# SHT_2_Power_07349-R5_L10.net
KiCad netlist of a schematic drawn in Altium Designer
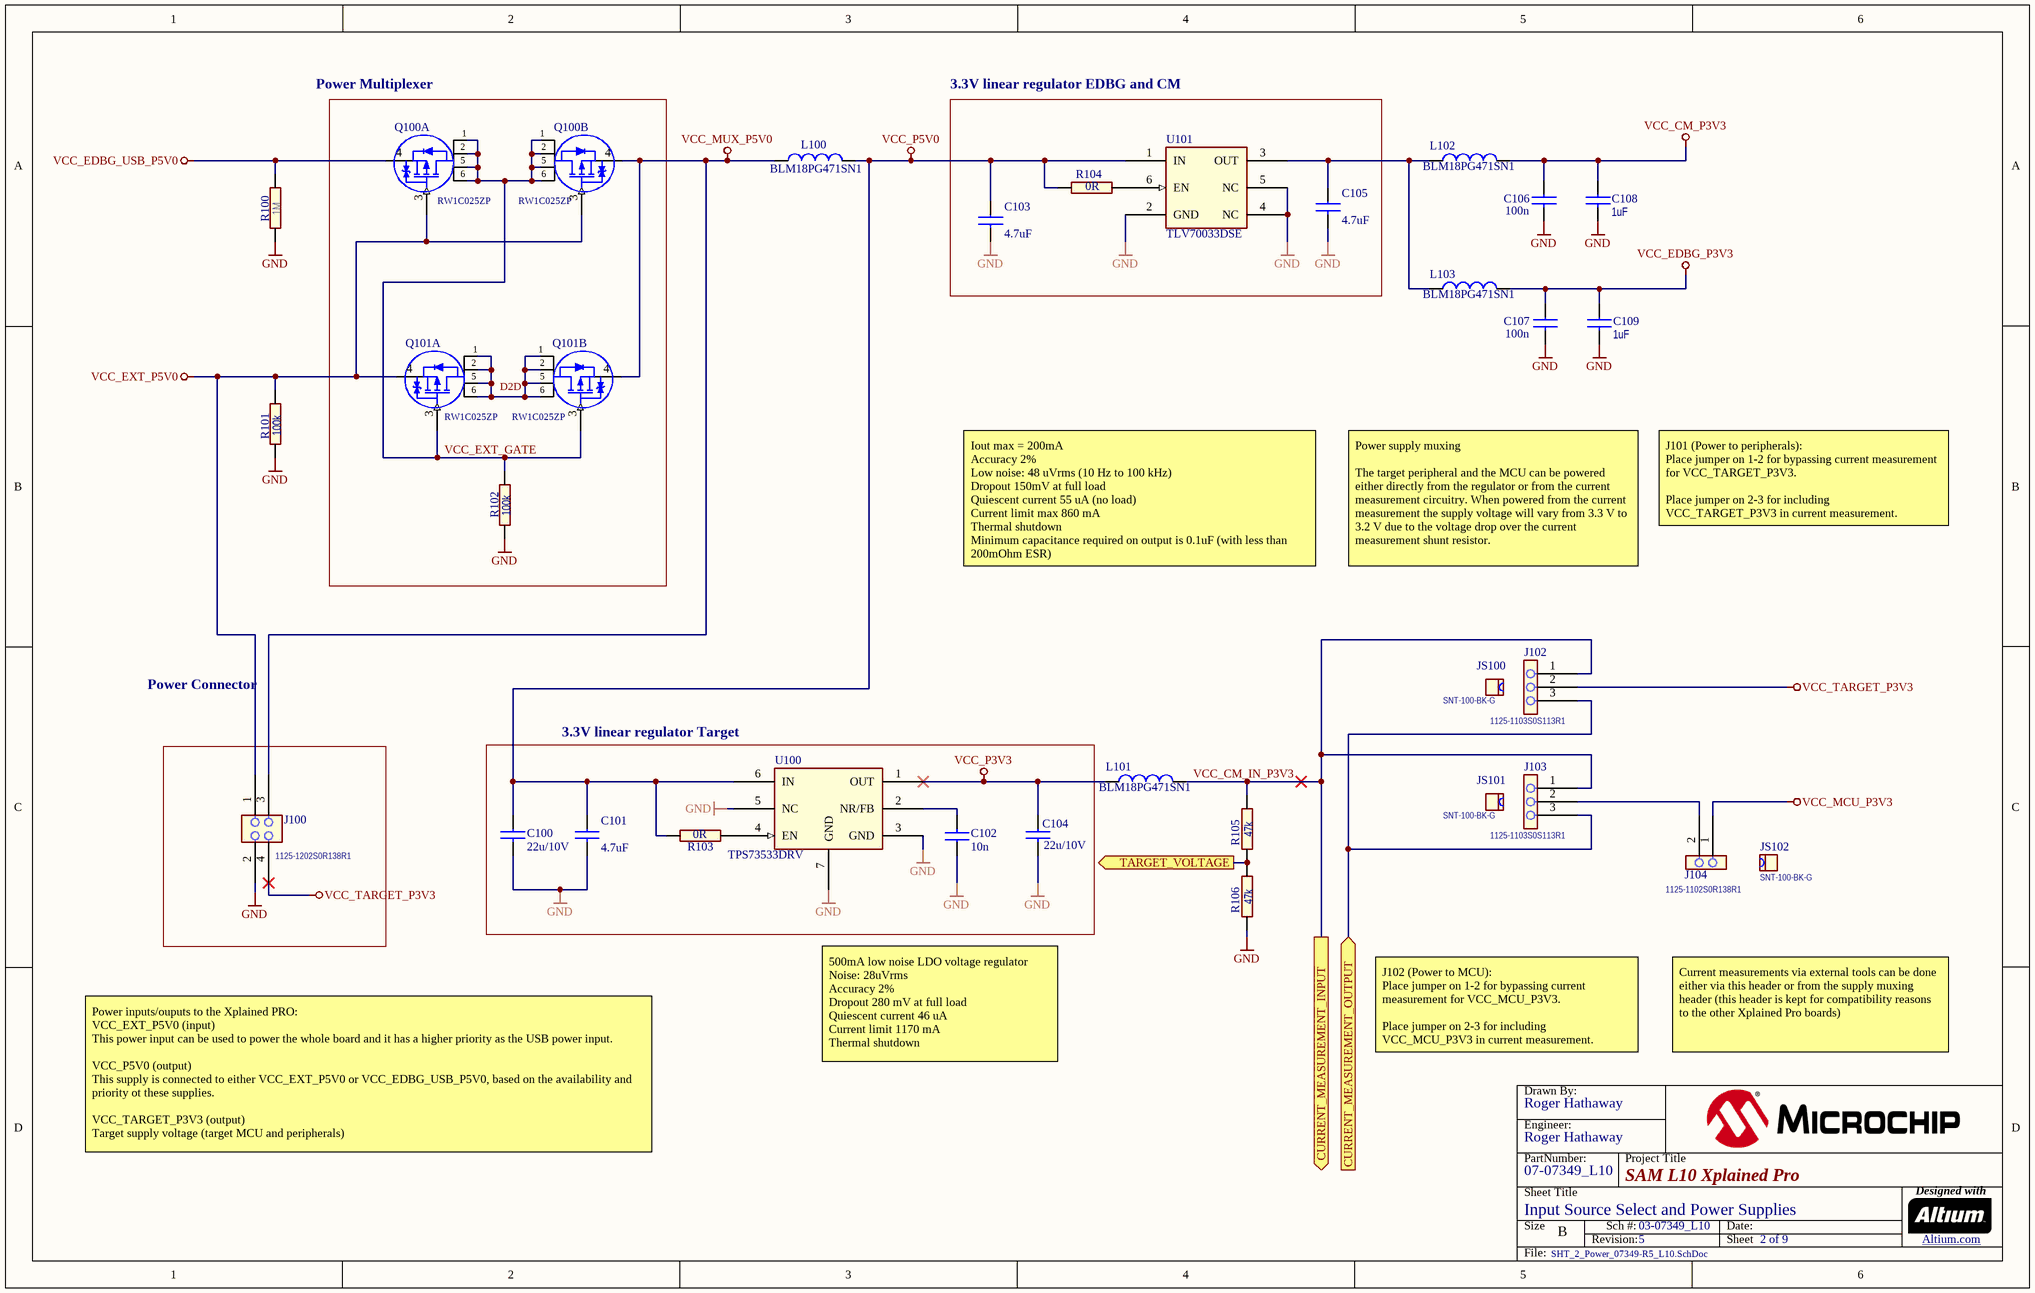
[diagram p0: SHT_2_Power_07349-R5_L10.SchDoc]

(export (version "E")
  (design (tool "Eeschema 10.0.6"))
  (components
    (comp (ref "C100")
      (value "22u/10V")
      (footprint "AP1-00003")
      (description "Ceramic capacitor, SMD 0805, X5R, 10V, Â±20%")
      (fields
        (field (name "MANUFACTURER") "tdk")
        (field (name "MPN") "C2012X5R1A226M/0.85")
        (field (name "VERIFIED BY") "Lars Helge Mo")
      )
      (libsource (lib "AltiumDbLib") (part "CAP-NONPOL"))
    )
    (comp (ref "C101")
      (value "4.7uF")
      (footprint "AltiumDbLib:AP1-00117")
      (description "Ceramic capacitor, SMD 0603, X5R, 10V, 10% (de31036)")
      (fields
        (field (name "TOLERANCE") "10%")
        (field (name "MANUFACTURER") "tdk")
        (field (name "VERIFIED BY") "Lars Helge Mo")
      )
      (libsource (lib "AltiumDbLib") (part "CAP-NONPOL"))
    )
    (comp (ref "C102")
      (value "10n")
      (footprint "AltiumDbLib:AP1-00053")
      (description "Ceramic capacitor, SMD 0402, X7R, 25V, +/-10%")
      (fields
        (field (name "TOLERANCE") "25V, +/-10%")
        (field (name "MANUFACTURER") "YAGEO CORP")
        (field (name "VERIFIED BY") "Lars Helge Mo")
      )
      (libsource (lib "AltiumDbLib") (part "CAP-NONPOL"))
    )
    (comp (ref "C103")
      (value "4.7uF")
      (footprint "AltiumDbLib:AP1-00117")
      (description "Ceramic capacitor, SMD 0603, X5R, 10V, 10% (de31036)")
      (fields
        (field (name "TOLERANCE") "10%")
        (field (name "MANUFACTURER") "tdk")
        (field (name "VERIFIED BY") "Lars Helge Mo")
      )
      (libsource (lib "AltiumDbLib") (part "CAP-NONPOL"))
    )
    (comp (ref "C104")
      (value "22u/10V")
      (footprint "AP1-00003")
      (description "Ceramic capacitor, SMD 0805, X5R, 10V, Â±20%")
      (fields
        (field (name "MANUFACTURER") "tdk")
        (field (name "MPN") "C2012X5R1A226M/0.85")
        (field (name "VERIFIED BY") "Lars Helge Mo")
      )
      (libsource (lib "AltiumDbLib") (part "CAP-NONPOL"))
    )
    (comp (ref "C105")
      (value "4.7uF")
      (footprint "AltiumDbLib:AP1-00117")
      (description "Ceramic capacitor, SMD 0603, X5R, 10V, 10% (de31036)")
      (fields
        (field (name "TOLERANCE") "10%")
        (field (name "MANUFACTURER") "tdk")
        (field (name "VERIFIED BY") "Lars Helge Mo")
      )
      (libsource (lib "AltiumDbLib") (part "CAP-NONPOL"))
    )
    (comp (ref "C106")
      (value "100n")
      (footprint "AltiumDbLib:AP1-00053")
      (description "Ceramic capacitor, SMD 0402, X7R, 16V, +/-10%")
      (fields
        (field (name "TOLERANCE") "16V, +/-10%")
        (field (name "MANUFACTURER") "Kemet")
        (field (name "VERIFIED BY") "Lars Helge Mo")
      )
      (libsource (lib "AltiumDbLib") (part "CAP-NONPOL"))
    )
    (comp (ref "C107")
      (value "100n")
      (footprint "AltiumDbLib:AP1-00053")
      (description "Ceramic capacitor, SMD 0402, X7R, 16V, +/-10%")
      (fields
        (field (name "TOLERANCE") "16V, +/-10%")
        (field (name "MANUFACTURER") "Kemet")
        (field (name "VERIFIED BY") "Lars Helge Mo")
      )
      (libsource (lib "AltiumDbLib") (part "CAP-NONPOL"))
    )
    (comp (ref "C108")
      (value "1uF")
      (footprint "AP1-00002")
      (description "Ceramic capacitor, SMD 0603, X5R, 25V, ±10%")
      (fields
        (field (name "TOLERANCE") "±10%")
        (field (name "MANUFACTURER") "Murata")
        (field (name "VERIFIED BY") "Lars Helge Mo")
      )
      (libsource (lib "AltiumDbLib") (part "CAP-NONPOL"))
    )
    (comp (ref "C109")
      (value "1uF")
      (footprint "AP1-00002")
      (description "Ceramic capacitor, SMD 0603, X5R, 25V, ±10%")
      (fields
        (field (name "TOLERANCE") "±10%")
        (field (name "MANUFACTURER") "Murata")
        (field (name "VERIFIED BY") "Lars Helge Mo")
      )
      (libsource (lib "AltiumDbLib") (part "CAP-NONPOL"))
    )
    (comp (ref "J100")
      (value "1125-1202S0R138R1")
      (footprint "AP8-01076")
      (description "Pin header, 2x2, Right Angle, 2.54mm, THT, Pin In Paste")
      (fields
        (field (name "MANUFACTURER") "WCON HARDWARE ELECTRONICS CO., LTD")
        (field (name "Comment") "HEADER 2x2")
        (field (name "VERIFIED BY") "Lars Helge Mo")
      )
      (libsource (lib "AltiumDbLib") (part "HEADER 2x2"))
    )
    (comp (ref "J102")
      (value "1125-1103S0S113R1")
      (footprint "AP8-01075")
      (description "1x3 pin header, 2.54mm pitch, Pin-in-Paste THM")
      (fields
        (field (name "MANUFACTURER") "WCON HARDWARE ELECTRONICS CO., LTD")
        (field (name "Comment") "HEADER 1x3")
        (field (name "VERIFIED BY") "Lars Helge Mo")
      )
      (libsource (lib "AltiumDbLib") (part "HEADER 1x3"))
    )
    (comp (ref "J103")
      (value "1125-1103S0S113R1")
      (footprint "AP8-01075")
      (description "1x3 pin header, 2.54mm pitch, Pin-in-Paste THM")
      (fields
        (field (name "MANUFACTURER") "WCON HARDWARE ELECTRONICS CO., LTD")
        (field (name "Comment") "HEADER 1x3")
        (field (name "VERIFIED BY") "Lars Helge Mo")
      )
      (libsource (lib "AltiumDbLib") (part "HEADER 1x3"))
    )
    (comp (ref "J104")
      (value "Low cost replacement for A08-0764")
      (footprint "AP8-01071")
      (description "1x2 pin header, right angle, 2.54 mm pitch, through-hole")
      (fields
        (field (name "MANUFACTURER") "WCON HARDWARE ELECTRONICS CO., LTD")
        (field (name "MPN") "1125-1102S0R138R1")
        (field (name "VERIFIED BY") "Lars Helge")
      )
      (libsource (lib "AltiumDbLib") (part "HEADER 1x2"))
    )
    (comp (ref "JS100")
      (value "SNT-100-BK-G")
      (footprint "AP8-00525")
      (description "Jumper cap for 2.54mm pinheader")
      (fields
        (field (name "MANUFACTURER") "SAMTEC")
        (field (name "Comment") "To be used by request from ESCATEC")
        (field (name "VERIFIED BY") "Lars Helge Mo")
      )
      (libsource (lib "AltiumDbLib") (part "JUMPER_CAP"))
    )
    (comp (ref "JS101")
      (value "SNT-100-BK-G")
      (footprint "AP8-00525")
      (description "Jumper cap for 2.54mm pinheader")
      (fields
        (field (name "MANUFACTURER") "SAMTEC")
        (field (name "Comment") "To be used by request from ESCATEC")
        (field (name "VERIFIED BY") "Lars Helge Mo")
      )
      (libsource (lib "AltiumDbLib") (part "JUMPER_CAP"))
    )
    (comp (ref "JS102")
      (value "SNT-100-BK-G")
      (footprint "AP8-00525")
      (description "Jumper cap for 2.54mm pinheader")
      (fields
        (field (name "MANUFACTURER") "SAMTEC")
        (field (name "Comment") "To be used by request from ESCATEC")
        (field (name "VERIFIED BY") "Lars Helge Mo")
      )
      (libsource (lib "") (part "JUMPER_CAP_1"))
    )
    (comp (ref "L100")
      (value "BLM18PG471SN1")
      (footprint "AP3-00005")
      (description "SMD RF inductor 0603. Z=470Ohm (@100MHz), Max R(dc)=0.65Ohm, Max current=1A")
      (fields
        (field (name "TOLERANCE") "±25%")
        (field (name "MANUFACTURER") "Murata")
        (field (name "VERIFIED BY") "Lars Helge Mo")
      )
      (libsource (lib "") (part "INDUCTOR_1"))
    )
    (comp (ref "L101")
      (value "BLM18PG471SN1")
      (footprint "AP3-00005")
      (description "SMD RF inductor 0603. Z=470Ohm (@100MHz), Max R(dc)=0.65Ohm, Max current=1A")
      (fields
        (field (name "TOLERANCE") "±25%")
        (field (name "MANUFACTURER") "Murata")
        (field (name "VERIFIED BY") "Lars Helge Mo")
      )
      (libsource (lib "AltiumDbLib") (part "INDUCTOR"))
    )
    (comp (ref "L102")
      (value "BLM18PG471SN1")
      (footprint "AP3-00005")
      (description "SMD RF inductor 0603. Z=470Ohm (@100MHz), Max R(dc)=0.65Ohm, Max current=1A")
      (fields
        (field (name "TOLERANCE") "±25%")
        (field (name "MANUFACTURER") "Murata")
        (field (name "VERIFIED BY") "Lars Helge Mo")
      )
      (libsource (lib "") (part "INDUCTOR_1"))
    )
    (comp (ref "L103")
      (value "BLM18PG471SN1")
      (footprint "AP3-00005")
      (description "SMD RF inductor 0603. Z=470Ohm (@100MHz), Max R(dc)=0.65Ohm, Max current=1A")
      (fields
        (field (name "TOLERANCE") "±25%")
        (field (name "MANUFACTURER") "Murata")
        (field (name "VERIFIED BY") "Lars Helge Mo")
      )
      (libsource (lib "") (part "INDUCTOR_1"))
    )
    (comp (ref "Q100A")
      (value "MOSFET_RW1C025ZP")
      (footprint "AP5-00057")
      (description "Pch -20V -2.5A Small Signal MOSFET")
      (fields
        (field (name "MANUFACTURER") "ROHM")
        (field (name "MPN") "RW1C025ZP")
        (field (name "MANUFACTURER PART NUMBER") "RW1C025ZP")
      )
      (libsource (lib "") (part "MOSFET_RW1C025ZP_1"))
    )
    (comp (ref "Q100B")
      (value "MOSFET_RW1C025ZP")
      (footprint "AP5-00057")
      (description "Pch -20V -2.5A Small Signal MOSFET")
      (fields
        (field (name "MANUFACTURER") "ROHM")
        (field (name "MPN") "RW1C025ZP")
        (field (name "MANUFACTURER PART NUMBER") "RW1C025ZP")
      )
      (libsource (lib "AltiumDbLib") (part "MOSFET_RW1C025ZP"))
    )
    (comp (ref "Q101A")
      (value "MOSFET_RW1C025ZP")
      (footprint "AP5-00057")
      (description "Pch -20V -2.5A Small Signal MOSFET")
      (fields
        (field (name "MANUFACTURER") "ROHM")
        (field (name "MPN") "RW1C025ZP")
        (field (name "MANUFACTURER PART NUMBER") "RW1C025ZP")
      )
      (libsource (lib "") (part "MOSFET_RW1C025ZP_1"))
    )
    (comp (ref "Q101B")
      (value "MOSFET_RW1C025ZP")
      (footprint "AP5-00057")
      (description "Pch -20V -2.5A Small Signal MOSFET")
      (fields
        (field (name "MANUFACTURER") "ROHM")
        (field (name "MPN") "RW1C025ZP")
        (field (name "MANUFACTURER PART NUMBER") "RW1C025ZP")
      )
      (libsource (lib "AltiumDbLib") (part "MOSFET_RW1C025ZP"))
    )
    (comp (ref "R100")
      (value "1M")
      (footprint "AltiumDbLib:AP2-00011")
      (description "Thick film resistror, SMD 0402, 1/16W, 1%")
      (fields
        (field (name "TOLERANCE") "1%")
        (field (name "MANUFACTURER") "YAGEO CORP")
        (field (name "VERIFIED BY") "Lars Helge Mo")
      )
      (libsource (lib "") (part "R2_2"))
    )
    (comp (ref "R101")
      (value "100k")
      (footprint "AltiumDbLib:AP2-00011")
      (description "Thick film resistor, SMD 0402, 1/16W, 1%")
      (fields
        (field (name "TOLERANCE") "1 %")
        (field (name "MANUFACTURER") "ASJ")
        (field (name "VERIFIED BY") "Lars Helge Mo")
      )
      (libsource (lib "") (part "R2_1"))
    )
    (comp (ref "R102")
      (value "100k")
      (footprint "AltiumDbLib:AP2-00011")
      (description "Thick film resistor, SMD 0402, 1/16W, 1%")
      (fields
        (field (name "TOLERANCE") "1 %")
        (field (name "MANUFACTURER") "ASJ")
        (field (name "VERIFIED BY") "Lars Helge Mo")
      )
      (libsource (lib "") (part "R2_1"))
    )
    (comp (ref "R103")
      (value "0R")
      (footprint "AltiumDbLib:AP2-00011")
      (description "RES 0.0 OHM 1/16W 0402 SMD")
      (fields
        (field (name "TOLERANCE") "1 %")
        (field (name "MANUFACTURER") "(n/a)")
        (field (name "VERIFIED BY") "Lars Helge Mo")
      )
      (libsource (lib "AltiumDbLib") (part "R2"))
    )
    (comp (ref "R104")
      (value "0R")
      (footprint "AltiumDbLib:AP2-00011")
      (description "RES 0.0 OHM 1/16W 0402 SMD")
      (fields
        (field (name "TOLERANCE") "1 %")
        (field (name "MANUFACTURER") "(n/a)")
        (field (name "VERIFIED BY") "Lars Helge Mo")
      )
      (libsource (lib "AltiumDbLib") (part "R2"))
    )
    (comp (ref "R105")
      (value "47k")
      (footprint "AltiumDbLib:AP2-00011")
      (description "Thick film resistor, SMD 0402, 1/16W, 1%")
      (fields
        (field (name "TOLERANCE") "1 %")
        (field (name "MANUFACTURER") "KOA")
        (field (name "VERIFIED BY") "Lars Helge Mo")
      )
      (libsource (lib "") (part "R2_1"))
    )
    (comp (ref "R106")
      (value "47k")
      (footprint "AltiumDbLib:AP2-00011")
      (description "Thick film resistor, SMD 0402, 1/16W, 1%")
      (fields
        (field (name "TOLERANCE") "1 %")
        (field (name "MANUFACTURER") "KOA")
        (field (name "VERIFIED BY") "Lars Helge Mo")
      )
      (libsource (lib "") (part "R2_1"))
    )
    (comp (ref "U100")
      (value "TPS73533DRV")
      (footprint "AP6-00162")
      (fields (field (name "MANUFACTURER") "Texas Instruments"))
      (libsource (lib "AltiumDbLib") (part "TPS735xxDRV"))
    )
    (comp (ref "U101")
      (value "TLV70033DSE")
      (footprint "AP6-00262")
      (description "LDO, 200 mA, Iq=31 uA, Vdo=250mV, Vout=3.3V, VIN= 2 V to 5.5V, SON-6 package")
      (fields (field (name "MANUFACTURER") "Texas Instruments"))
      (libsource (lib "AltiumDbLib") (part "TLV70033"))
    )
  )
  (nets
    (net (code "1") (name "/CURRENT_MEASUREMENT_OUTPUT") (class "Default")
      (node (ref "J102") (pin "3") (pinfunction "3_3") (pintype "passive"))
      (node (ref "J103") (pin "3") (pinfunction "3_3") (pintype "passive"))
    )
    (net (code "3") (name "/TARGET_VOLTAGE") (class "Default")
      (node (ref "R105") (pin "1") (pinfunction "1_1") (pintype "passive"))
      (node (ref "R106") (pin "2") (pinfunction "2_2") (pintype "passive"))
    )
    (net (code "4") (name "/VCC_CM_IN_P3V3") (class "Default")
      (node (ref "J102") (pin "1") (pinfunction "1_1") (pintype "passive"))
      (node (ref "J103") (pin "1") (pinfunction "1_1") (pintype "passive"))
      (node (ref "L101") (pin "1") (pinfunction "1_1") (pintype "passive"))
      (node (ref "R105") (pin "2") (pinfunction "2_2") (pintype "passive"))
    )
    (net (code "5") (name "/VCC_EXT_GATE") (class "Default")
      (node (ref "Q100A") (pin "1") (pinfunction "D_1") (pintype "passive"))
      (node (ref "Q100A") (pin "2") (pinfunction "D_2") (pintype "passive"))
      (node (ref "Q100A") (pin "5") (pinfunction "D_5") (pintype "passive"))
      (node (ref "Q100A") (pin "6") (pinfunction "D_6") (pintype "passive"))
      (node (ref "Q100B") (pin "1") (pinfunction "D_1") (pintype "passive"))
      (node (ref "Q100B") (pin "2") (pinfunction "D_2") (pintype "passive"))
      (node (ref "Q100B") (pin "5") (pinfunction "D_5") (pintype "passive"))
      (node (ref "Q100B") (pin "6") (pinfunction "D_6") (pintype "passive"))
      (node (ref "Q101A") (pin "3") (pinfunction "G_3") (pintype "input"))
      (node (ref "Q101B") (pin "3") (pinfunction "G_3") (pintype "input"))
      (node (ref "R102") (pin "2") (pinfunction "2_2") (pintype "passive"))
    )
    (net (code "6") (name "GND") (class "Default")
      (node (ref "C100") (pin "2") (pinfunction "2_2") (pintype "passive"))
      (node (ref "C101") (pin "2") (pinfunction "2_2") (pintype "passive"))
      (node (ref "C102") (pin "1") (pinfunction "1_1") (pintype "passive"))
      (node (ref "C103") (pin "2") (pinfunction "2_2") (pintype "passive"))
      (node (ref "C104") (pin "2") (pinfunction "2_2") (pintype "passive"))
      (node (ref "C105") (pin "2") (pinfunction "2_2") (pintype "passive"))
      (node (ref "C106") (pin "2") (pinfunction "2_2") (pintype "passive"))
      (node (ref "C107") (pin "2") (pinfunction "2_2") (pintype "passive"))
      (node (ref "C108") (pin "2") (pinfunction "2_2") (pintype "passive"))
      (node (ref "C109") (pin "2") (pinfunction "2_2") (pintype "passive"))
      (node (ref "J100") (pin "2") (pinfunction "2_2") (pintype "passive"))
      (node (ref "R100") (pin "2") (pinfunction "2_2") (pintype "passive"))
      (node (ref "R101") (pin "1") (pinfunction "1_1") (pintype "passive"))
      (node (ref "R102") (pin "1") (pinfunction "1_1") (pintype "passive"))
      (node (ref "R106") (pin "1") (pinfunction "1_1") (pintype "passive"))
      (node (ref "U100") (pin "3") (pinfunction "GND_3") (pintype "power_in"))
      (node (ref "U100") (pin "5") (pinfunction "NC_5") (pintype "passive"))
      (node (ref "U100") (pin "7") (pinfunction "GND_7") (pintype "power_in"))
      (node (ref "U101") (pin "2") (pinfunction "GND_2") (pintype "power_in"))
      (node (ref "U101") (pin "4") (pinfunction "NC_4") (pintype "passive"))
      (node (ref "U101") (pin "5") (pinfunction "NC_5") (pintype "passive"))
    )
    (net (code "7") (name "Net-(J103-Pad2)") (class "Default")
      (node (ref "J103") (pin "2") (pinfunction "2_2") (pintype "passive"))
      (node (ref "J104") (pin "2") (pinfunction "2_2") (pintype "passive"))
    )
    (net (code "8") (name "Net-(Q101A-D-Pad1)") (class "Default")
      (node (ref "Q101A") (pin "1") (pinfunction "D_1") (pintype "passive"))
      (node (ref "Q101A") (pin "2") (pinfunction "D_2") (pintype "passive"))
      (node (ref "Q101A") (pin "5") (pinfunction "D_5") (pintype "passive"))
      (node (ref "Q101A") (pin "6") (pinfunction "D_6") (pintype "passive"))
      (node (ref "Q101B") (pin "1") (pinfunction "D_1") (pintype "passive"))
      (node (ref "Q101B") (pin "2") (pinfunction "D_2") (pintype "passive"))
      (node (ref "Q101B") (pin "5") (pinfunction "D_5") (pintype "passive"))
      (node (ref "Q101B") (pin "6") (pinfunction "D_6") (pintype "passive"))
    )
    (net (code "9") (name "Net-(U100-EN)") (class "Default")
      (node (ref "R103") (pin "1") (pinfunction "1_1") (pintype "passive"))
      (node (ref "U100") (pin "4") (pinfunction "EN_4") (pintype "input"))
    )
    (net (code "10") (name "Net-(U100-NR{slash}FB)") (class "Default")
      (node (ref "C102") (pin "2") (pinfunction "2_2") (pintype "passive"))
      (node (ref "U100") (pin "2") (pinfunction "NR/FB_2") (pintype "passive"))
    )
    (net (code "11") (name "Net-(U101-EN)") (class "Default")
      (node (ref "R104") (pin "1") (pinfunction "1_1") (pintype "passive"))
      (node (ref "U101") (pin "6") (pinfunction "EN_6") (pintype "input"))
    )
    (net (code "12") (name "Net-(U101-OUT)") (class "Default")
      (node (ref "C105") (pin "1") (pinfunction "1_1") (pintype "passive"))
      (node (ref "L102") (pin "1") (pinfunction "1_1") (pintype "passive"))
      (node (ref "L103") (pin "1") (pinfunction "1_1") (pintype "passive"))
      (node (ref "U101") (pin "3") (pinfunction "OUT_3") (pintype "power_in"))
    )
    (net (code "13") (name "VCC_CM_P3V3") (class "Default")
      (node (ref "C106") (pin "1") (pinfunction "1_1") (pintype "passive"))
      (node (ref "C108") (pin "1") (pinfunction "1_1") (pintype "passive"))
      (node (ref "L102") (pin "2") (pinfunction "2_2") (pintype "passive"))
    )
    (net (code "14") (name "VCC_EDBG_P3V3") (class "Default")
      (node (ref "C107") (pin "1") (pinfunction "1_1") (pintype "passive"))
      (node (ref "C109") (pin "1") (pinfunction "1_1") (pintype "passive"))
      (node (ref "L103") (pin "2") (pinfunction "2_2") (pintype "passive"))
    )
    (net (code "15") (name "VCC_EDBG_USB_P5V0") (class "Default")
      (node (ref "Q100A") (pin "4") (pinfunction "S_4") (pintype "passive"))
      (node (ref "R100") (pin "1") (pinfunction "1_1") (pintype "passive"))
    )
    (net (code "16") (name "VCC_EXT_P5V0") (class "Default")
      (node (ref "J100") (pin "1") (pinfunction "1_1") (pintype "passive"))
      (node (ref "Q100A") (pin "3") (pinfunction "G_3") (pintype "input"))
      (node (ref "Q100B") (pin "3") (pinfunction "G_3") (pintype "input"))
      (node (ref "Q101A") (pin "4") (pinfunction "S_4") (pintype "passive"))
      (node (ref "R101") (pin "2") (pinfunction "2_2") (pintype "passive"))
    )
    (net (code "17") (name "VCC_MCU_P3V3") (class "Default")
      (node (ref "J104") (pin "1") (pinfunction "1_1") (pintype "passive"))
    )
    (net (code "18") (name "VCC_MUX_P5V0") (class "Default")
      (node (ref "J100") (pin "3") (pinfunction "3_3") (pintype "passive"))
      (node (ref "L100") (pin "1") (pinfunction "1_1") (pintype "passive"))
      (node (ref "Q100B") (pin "4") (pinfunction "S_4") (pintype "passive"))
      (node (ref "Q101B") (pin "4") (pinfunction "S_4") (pintype "passive"))
    )
    (net (code "19") (name "VCC_P3V3") (class "Default")
      (node (ref "C104") (pin "1") (pinfunction "1_1") (pintype "passive"))
      (node (ref "L101") (pin "2") (pinfunction "2_2") (pintype "passive"))
      (node (ref "U100") (pin "1") (pinfunction "OUT_1") (pintype "power_in"))
    )
    (net (code "20") (name "VCC_P5V0") (class "Default")
      (node (ref "C100") (pin "1") (pinfunction "1_1") (pintype "passive"))
      (node (ref "C101") (pin "1") (pinfunction "1_1") (pintype "passive"))
      (node (ref "C103") (pin "1") (pinfunction "1_1") (pintype "passive"))
      (node (ref "L100") (pin "2") (pinfunction "2_2") (pintype "passive"))
      (node (ref "R103") (pin "2") (pinfunction "2_2") (pintype "passive"))
      (node (ref "R104") (pin "2") (pinfunction "2_2") (pintype "passive"))
      (node (ref "U100") (pin "6") (pinfunction "IN_6") (pintype "power_in"))
      (node (ref "U101") (pin "1") (pinfunction "IN_1") (pintype "power_in"))
    )
    (net (code "21") (name "VCC_TARGET_P3V3") (class "Default")
      (node (ref "J100") (pin "4") (pinfunction "4_4") (pintype "passive"))
      (node (ref "J102") (pin "2") (pinfunction "2_2") (pintype "passive"))
    )
  )
)
